# LED_adapt.net
KiCad netlist of a schematic drawn in Altium Designer
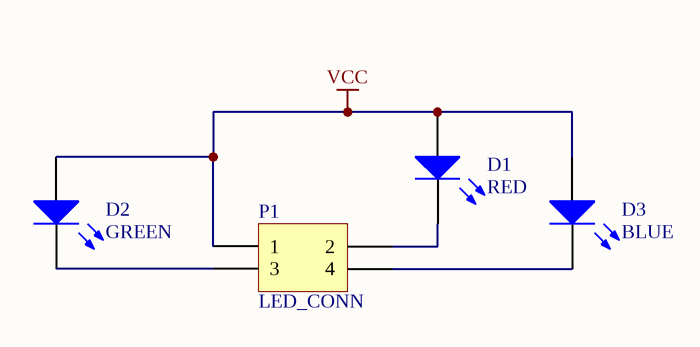
[diagram p0: LED_adapt.SchDoc]

(export (version "E")
  (design (tool "Eeschema 10.0.6"))
  (components
    (comp (ref "D1")
      (value "RED")
      (footprint "LED-0")
      (description "Typical INFRARED GaAs LED")
      (fields (field (name "PUBLISHER") "Altium Limited"))
      (libsource (lib "Miscellaneous Devices") (part "LED0"))
    )
    (comp (ref "D2")
      (value "GREEN")
      (footprint "LED-0")
      (description "Typical INFRARED GaAs LED")
      (fields (field (name "PUBLISHER") "Altium Limited"))
      (libsource (lib "Miscellaneous Devices") (part "LED0"))
    )
    (comp (ref "D3")
      (value "BLUE")
      (footprint "LED-0")
      (description "Typical INFRARED GaAs LED")
      (fields (field (name "PUBLISHER") "Altium Limited"))
      (libsource (lib "Miscellaneous Devices") (part "LED0"))
    )
    (comp (ref "P1")
      (value "LED_CONN")
      (footprint "HDR2X2")
      (description "Header, 2-Pin, Dual row")
      (fields (field (name "PUBLISHER") "Altium Limited"))
      (libsource (lib "Miscellaneous Connectors") (part "Header 2X2"))
    )
  )
  (nets
    (net (code "1") (name "Net-(D1-K)") (class "Default")
      (node (ref "D1") (pin "2") (pinfunction "K_2") (pintype "passive"))
      (node (ref "P1") (pin "2") (pinfunction "2_2") (pintype "passive"))
    )
    (net (code "2") (name "Net-(D2-K)") (class "Default")
      (node (ref "D2") (pin "2") (pinfunction "K_2") (pintype "passive"))
      (node (ref "P1") (pin "3") (pinfunction "3_3") (pintype "passive"))
    )
    (net (code "3") (name "Net-(D3-K)") (class "Default")
      (node (ref "D3") (pin "2") (pinfunction "K_2") (pintype "passive"))
      (node (ref "P1") (pin "4") (pinfunction "4_4") (pintype "passive"))
    )
    (net (code "4") (name "VCC") (class "Default")
      (node (ref "D1") (pin "1") (pinfunction "A_1") (pintype "passive"))
      (node (ref "D2") (pin "1") (pinfunction "A_1") (pintype "passive"))
      (node (ref "D3") (pin "1") (pinfunction "A_1") (pintype "passive"))
      (node (ref "P1") (pin "1") (pinfunction "1_1") (pintype "passive"))
    )
  )
)
